# V2.net
KiCad netlist of a schematic drawn in EAGLE
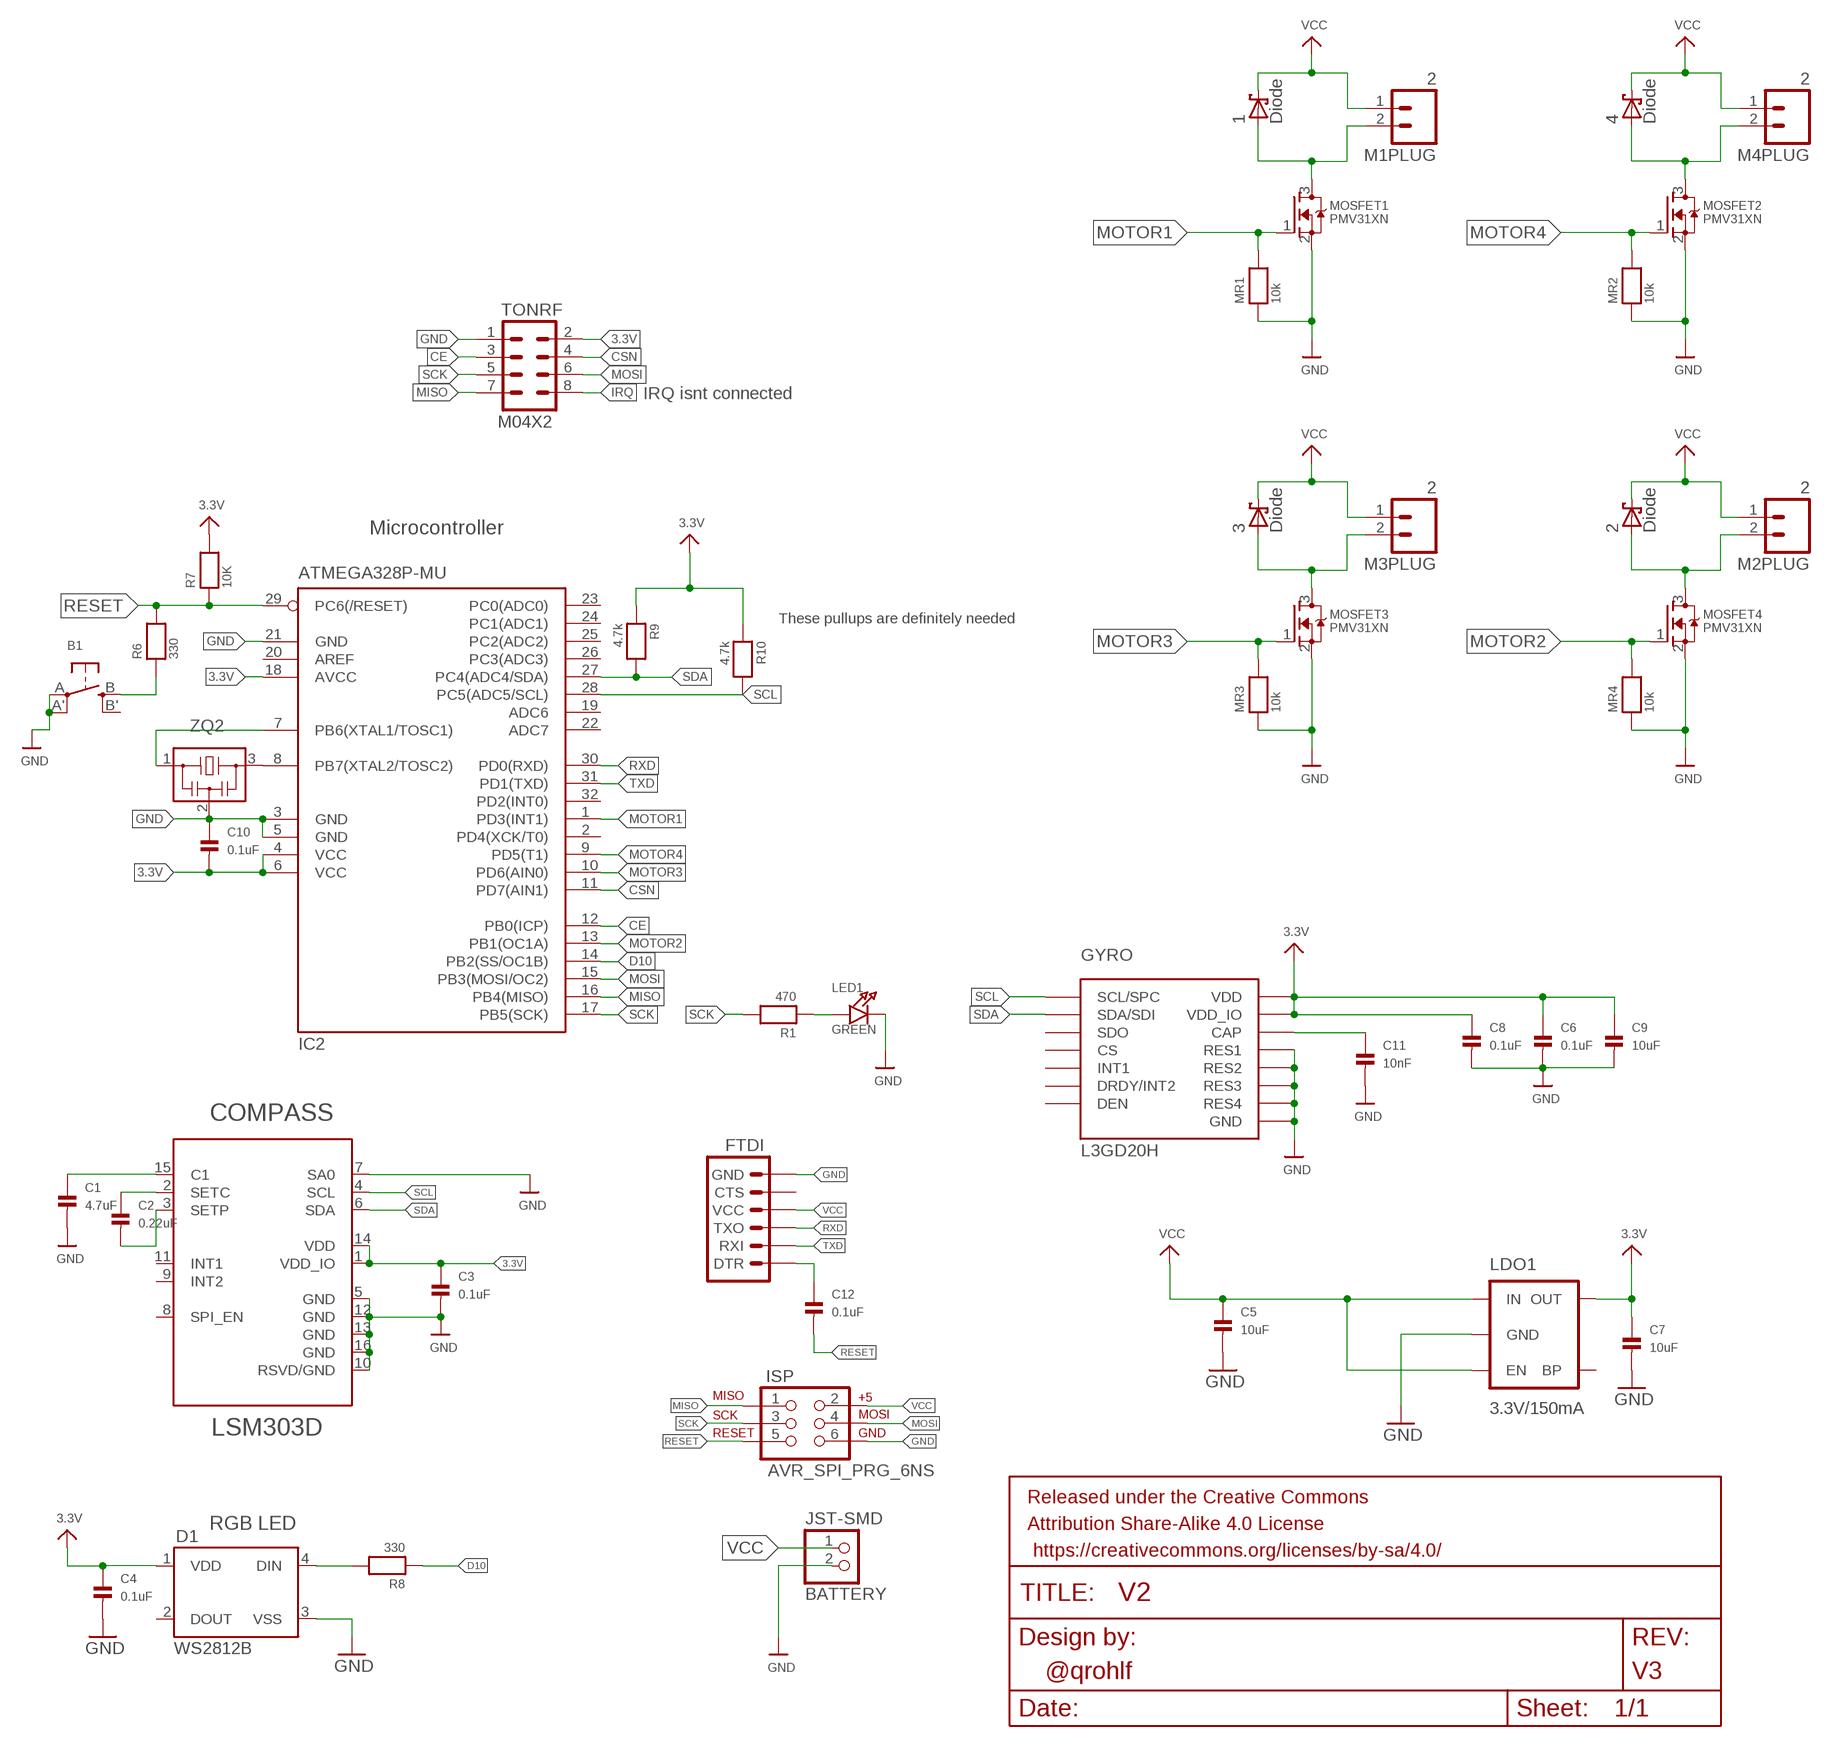
[diagram p0: schematic, sheet 1]

(export (version "E")
  (design (tool "Eeschema 10.0.6"))
  (components
    (comp (ref "1")
      (value "Diode")
      (footprint "eagle-import:SOT23")
      (libsource (lib "eagle-import") (part "BAS40"))
    )
    (comp (ref "2")
      (value "Diode")
      (footprint "eagle-import:SOT23")
      (libsource (lib "eagle-import") (part "BAS40"))
    )
    (comp (ref "3")
      (value "Diode")
      (footprint "eagle-import:SOT23")
      (libsource (lib "eagle-import") (part "BAS40"))
    )
    (comp (ref "4")
      (value "Diode")
      (footprint "eagle-import:SOT23")
      (libsource (lib "eagle-import") (part "BAS40"))
    )
    (comp (ref "B1")
      (value "SWITCH_TACT_SMT4.6X2.8")
      (footprint "eagle-import:BTN_KMR2_4.6X2.8")
      (libsource (lib "eagle-import") (part "SWITCH_TACT_SMT4.6X2.8"))
    )
    (comp (ref "BATTERY")
      (value "JST-SMD")
      (footprint "eagle-import:JST-PH-2-SMT-RA")
      (libsource (lib "eagle-import") (part "JST_2PIN-SMT-RA"))
    )
    (comp (ref "C1")
      (value "4.7uF")
      (footprint "eagle-import:0603-MINI")
      (libsource (lib "eagle-import") (part "CAP_CERAMIC0603MINI"))
    )
    (comp (ref "C2")
      (value "0.22uF")
      (footprint "eagle-import:0603-MINI")
      (libsource (lib "eagle-import") (part "CAP_CERAMIC0603MINI"))
    )
    (comp (ref "C3")
      (value "0.1uF")
      (footprint "eagle-import:0603-MINI")
      (libsource (lib "eagle-import") (part "CAP_CERAMIC0603MINI"))
    )
    (comp (ref "C4")
      (value "0.1uF")
      (footprint "eagle-import:0603-MINI")
      (libsource (lib "eagle-import") (part "CAP_CERAMIC0603MINI"))
    )
    (comp (ref "C5")
      (value "10uF")
      (footprint "eagle-import:0603-MINI")
      (libsource (lib "eagle-import") (part "CAP_CERAMIC0603MINI"))
    )
    (comp (ref "C6")
      (value "0.1uF")
      (footprint "eagle-import:0603-MINI")
      (libsource (lib "eagle-import") (part "CAP_CERAMIC0603MINI"))
    )
    (comp (ref "C7")
      (value "10uF")
      (footprint "eagle-import:0603-MINI")
      (libsource (lib "eagle-import") (part "CAP_CERAMIC0603MINI"))
    )
    (comp (ref "C8")
      (value "0.1uF")
      (footprint "eagle-import:0603-MINI")
      (libsource (lib "eagle-import") (part "CAP_CERAMIC0603MINI"))
    )
    (comp (ref "C9")
      (value "10uF")
      (footprint "eagle-import:0603-MINI")
      (libsource (lib "eagle-import") (part "CAP_CERAMIC0603MINI"))
    )
    (comp (ref "C10")
      (value "0.1uF")
      (footprint "eagle-import:0603-MINI")
      (libsource (lib "eagle-import") (part "CAP_CERAMIC0603MINI"))
    )
    (comp (ref "C11")
      (value "10nF")
      (footprint "eagle-import:0603-MINI")
      (libsource (lib "eagle-import") (part "CAP_CERAMIC0603MINI"))
    )
    (comp (ref "C12")
      (value "0.1uF")
      (footprint "eagle-import:0603-MINI")
      (libsource (lib "eagle-import") (part "CAP_CERAMIC0603MINI"))
    )
    (comp (ref "COMPASS")
      (value "LSM303D")
      (footprint "eagle-import:LGA16_3X5")
      (libsource (lib "eagle-import") (part "LSM303D"))
    )
    (comp (ref "D1")
      (value "WS2812B")
      (footprint "eagle-import:WS2812B")
      (libsource (lib "eagle-import") (part "WS2812B"))
    )
    (comp (ref "FRAME1")
      (value ">VERSION")
      (footprint "eagle-import:DUMMY")
      (fields (field (name "DESIGNER") "@qrohlf") (field (name "VERSION") "V3"))
      (libsource (lib "eagle-import") (part "FRAME-LETTERNO_PACKAGE"))
    )
    (comp (ref "FTDI")
      (value "ARDUINO_SERIAL_PROGRAMLOCK")
      (footprint "eagle-import:1X06_LOCK")
      (libsource (lib "eagle-import") (part "ARDUINO_SERIAL_PROGRAMLOCK"))
    )
    (comp (ref "IC2")
      (value "ATMEGA328P-MU")
      (footprint "eagle-import:TQFP32-08")
      (fields (field (name "MPN") "ATMEGA8-16AU"))
      (libsource (lib "eagle-import") (part "MEGA8-AI"))
    )
    (comp (ref "ISP")
      (value "AVR_SPI_PRG_6NS")
      (footprint "eagle-import:2X3-NS")
      (libsource (lib "eagle-import") (part "AVR_SPI_PRG_6NS"))
    )
    (comp (ref "L3GD20H")
      (value "L3GD20H")
      (footprint "eagle-import:LGA16L")
      (libsource (lib "eagle-import") (part "L3GD20H"))
    )
    (comp (ref "LDO1")
      (value "3.3V/150mA")
      (footprint "eagle-import:SOT23-5")
      (libsource (lib "eagle-import") (part "V_REG_MIC52053.3V"))
    )
    (comp (ref "LED1")
      (value "GREEN")
      (footprint "eagle-import:CHIPLED_0603")
      (libsource (lib "eagle-import") (part "LED0603"))
    )
    (comp (ref "M1PLUG")
      (value "2")
      (footprint "eagle-import:MOLEX-1X2_LOCK")
      (libsource (lib "eagle-import") (part "M02POLAR_LOCK"))
    )
    (comp (ref "M2PLUG")
      (value "2")
      (footprint "eagle-import:MOLEX-1X2_LOCK")
      (libsource (lib "eagle-import") (part "M02POLAR_LOCK"))
    )
    (comp (ref "M3PLUG")
      (value "2")
      (footprint "eagle-import:MOLEX-1X2_LOCK")
      (libsource (lib "eagle-import") (part "M02POLAR_LOCK"))
    )
    (comp (ref "M4PLUG")
      (value "2")
      (footprint "eagle-import:MOLEX-1X2_LOCK")
      (libsource (lib "eagle-import") (part "M02POLAR_LOCK"))
    )
    (comp (ref "MOSFET1")
      (value "PMV31XN")
      (footprint "eagle-import:SOT23-R")
      (libsource (lib "eagle-import") (part "MOSFET-NREFLOW"))
    )
    (comp (ref "MOSFET2")
      (value "PMV31XN")
      (footprint "eagle-import:SOT23-R")
      (libsource (lib "eagle-import") (part "MOSFET-NREFLOW"))
    )
    (comp (ref "MOSFET3")
      (value "PMV31XN")
      (footprint "eagle-import:SOT23-R")
      (libsource (lib "eagle-import") (part "MOSFET-NREFLOW"))
    )
    (comp (ref "MOSFET4")
      (value "PMV31XN")
      (footprint "eagle-import:SOT23-R")
      (libsource (lib "eagle-import") (part "MOSFET-NREFLOW"))
    )
    (comp (ref "MR1")
      (value "10k")
      (footprint "eagle-import:0603-MINI")
      (libsource (lib "eagle-import") (part "RESISTOR0603MINI"))
    )
    (comp (ref "MR2")
      (value "10k")
      (footprint "eagle-import:0603-MINI")
      (libsource (lib "eagle-import") (part "RESISTOR0603MINI"))
    )
    (comp (ref "MR3")
      (value "10k")
      (footprint "eagle-import:0603-MINI")
      (libsource (lib "eagle-import") (part "RESISTOR0603MINI"))
    )
    (comp (ref "MR4")
      (value "10k")
      (footprint "eagle-import:0603-MINI")
      (libsource (lib "eagle-import") (part "RESISTOR0603MINI"))
    )
    (comp (ref "R1")
      (value "470")
      (footprint "eagle-import:0603-MINI")
      (libsource (lib "eagle-import") (part "RESISTOR0603MINI"))
    )
    (comp (ref "R6")
      (value "330")
      (footprint "eagle-import:0603-MINI")
      (libsource (lib "eagle-import") (part "RESISTOR0603MINI"))
    )
    (comp (ref "R7")
      (value "10K")
      (footprint "eagle-import:0603-MINI")
      (libsource (lib "eagle-import") (part "RESISTOR0603MINI"))
    )
    (comp (ref "R8")
      (value "330")
      (footprint "eagle-import:0603-MINI")
      (libsource (lib "eagle-import") (part "RESISTOR0603MINI"))
    )
    (comp (ref "R9")
      (value "4.7k")
      (footprint "eagle-import:0603-MINI")
      (libsource (lib "eagle-import") (part "RESISTOR0603MINI"))
    )
    (comp (ref "R10")
      (value "4.7k")
      (footprint "eagle-import:0603-MINI")
      (libsource (lib "eagle-import") (part "RESISTOR0603MINI"))
    )
    (comp (ref "TONRF")
      (value "M04X2")
      (footprint "eagle-import:2X4")
      (libsource (lib "eagle-import") (part "M04X2"))
    )
    (comp (ref "ZQ2")
      (value "CSTCE8M00G52-R0")
      (footprint "eagle-import:CSTCE")
      (libsource (lib "eagle-import") (part "CSTC?E8M00G52-R0"))
    )
  )
  (nets
    (net (code "1") (name "3.3V") (class "Default")
      (node (ref "C10") (pin "2") (pinfunction "P$2_2") (pintype "passive"))
      (node (ref "C3") (pin "1") (pinfunction "P$1_1") (pintype "passive"))
      (node (ref "C4") (pin "1") (pinfunction "P$1_1") (pintype "passive"))
      (node (ref "C6") (pin "1") (pinfunction "P$1_1") (pintype "passive"))
      (node (ref "C7") (pin "1") (pinfunction "P$1_1") (pintype "passive"))
      (node (ref "C8") (pin "1") (pinfunction "P$1_1") (pintype "passive"))
      (node (ref "C9") (pin "1") (pinfunction "P$1_1") (pintype "passive"))
      (node (ref "COMPASS") (pin "1") (pinfunction "VDD_IO_1") (pintype "power_in"))
      (node (ref "COMPASS") (pin "14") (pinfunction "VDD_14") (pintype "power_in"))
      (node (ref "D1") (pin "1") (pinfunction "VDD_1") (pintype "power_in"))
      (node (ref "IC2") (pin "18") (pinfunction "AVCC_18") (pintype "power_in"))
      (node (ref "IC2") (pin "4") (pinfunction "VCC_4") (pintype "power_in"))
      (node (ref "IC2") (pin "6") (pinfunction "VCC_6") (pintype "power_in"))
      (node (ref "L3GD20H") (pin "P$1") (pinfunction "VDD_IO_P$1") (pintype "power_in"))
      (node (ref "L3GD20H") (pin "P$16") (pinfunction "VDD_P$16") (pintype "power_in"))
      (node (ref "LDO1") (pin "5") (pinfunction "OUT_5") (pintype "passive"))
      (node (ref "R10") (pin "1") (pinfunction "1_1") (pintype "passive"))
      (node (ref "R7") (pin "2") (pinfunction "2_2") (pintype "passive"))
      (node (ref "R9") (pin "1") (pinfunction "1_1") (pintype "passive"))
      (node (ref "TONRF") (pin "2") (pinfunction "2_2") (pintype "passive"))
    )
    (net (code "2") (name "CE") (class "Default")
      (node (ref "IC2") (pin "12") (pinfunction "PB0(ICP)_12") (pintype "bidirectional"))
      (node (ref "TONRF") (pin "3") (pinfunction "3_3") (pintype "passive"))
    )
    (net (code "3") (name "CSN") (class "Default")
      (node (ref "IC2") (pin "11") (pinfunction "PD7(AIN1)_11") (pintype "bidirectional"))
      (node (ref "TONRF") (pin "4") (pinfunction "4_4") (pintype "passive"))
    )
    (net (code "4") (name "D10") (class "Default")
      (node (ref "IC2") (pin "14") (pinfunction "PB2(SS/OC1B)_14") (pintype "bidirectional"))
      (node (ref "R8") (pin "1") (pinfunction "1_1") (pintype "passive"))
    )
    (net (code "5") (name "GND") (class "Default")
      (node (ref "B1") (pin "A") (pinfunction "P_A") (pintype "passive"))
      (node (ref "B1") (pin "A'") (pinfunction "P1_A'") (pintype "passive"))
      (node (ref "BATTERY") (pin "2") (pinfunction "1_2") (pintype "passive"))
      (node (ref "C1") (pin "2") (pinfunction "P$2_2") (pintype "passive"))
      (node (ref "C10") (pin "1") (pinfunction "P$1_1") (pintype "passive"))
      (node (ref "C11") (pin "2") (pinfunction "P$2_2") (pintype "passive"))
      (node (ref "C3") (pin "2") (pinfunction "P$2_2") (pintype "passive"))
      (node (ref "C4") (pin "2") (pinfunction "P$2_2") (pintype "passive"))
      (node (ref "C5") (pin "2") (pinfunction "P$2_2") (pintype "passive"))
      (node (ref "C6") (pin "2") (pinfunction "P$2_2") (pintype "passive"))
      (node (ref "C7") (pin "2") (pinfunction "P$2_2") (pintype "passive"))
      (node (ref "C8") (pin "2") (pinfunction "P$2_2") (pintype "passive"))
      (node (ref "C9") (pin "2") (pinfunction "P$2_2") (pintype "passive"))
      (node (ref "COMPASS") (pin "10") (pinfunction "RSVD/GND_10") (pintype "bidirectional"))
      (node (ref "COMPASS") (pin "12") (pinfunction "GND_12") (pintype "power_in"))
      (node (ref "COMPASS") (pin "13") (pinfunction "GND_13") (pintype "power_in"))
      (node (ref "COMPASS") (pin "16") (pinfunction "GND_16") (pintype "power_in"))
      (node (ref "COMPASS") (pin "5") (pinfunction "GND_5") (pintype "power_in"))
      (node (ref "COMPASS") (pin "7") (pinfunction "SA0_7") (pintype "bidirectional"))
      (node (ref "D1") (pin "3") (pinfunction "VSS_3") (pintype "power_in"))
      (node (ref "FTDI") (pin "6") (pinfunction "GND_6") (pintype "passive"))
      (node (ref "IC2") (pin "21") (pinfunction "GND_21") (pintype "power_in"))
      (node (ref "IC2") (pin "3") (pinfunction "GND_3") (pintype "power_in"))
      (node (ref "IC2") (pin "5") (pinfunction "GND_5") (pintype "power_in"))
      (node (ref "ISP") (pin "6") (pinfunction "6_6") (pintype "passive"))
      (node (ref "L3GD20H") (pin "P$10") (pinfunction "RES2_P$10") (pintype "bidirectional"))
      (node (ref "L3GD20H") (pin "P$11") (pinfunction "RES3_P$11") (pintype "bidirectional"))
      (node (ref "L3GD20H") (pin "P$12") (pinfunction "GND_P$12") (pintype "power_in"))
      (node (ref "L3GD20H") (pin "P$13") (pinfunction "GND_P$13") (pintype "power_in"))
      (node (ref "L3GD20H") (pin "P$15") (pinfunction "RES4_P$15") (pintype "bidirectional"))
      (node (ref "L3GD20H") (pin "P$9") (pinfunction "RES1_P$9") (pintype "bidirectional"))
      (node (ref "LDO1") (pin "2") (pinfunction "GND_2") (pintype "input"))
      (node (ref "LED1") (pin "C") (pinfunction "C_C") (pintype "passive"))
      (node (ref "MOSFET1") (pin "2") (pinfunction "S_2") (pintype "bidirectional"))
      (node (ref "MOSFET2") (pin "2") (pinfunction "S_2") (pintype "bidirectional"))
      (node (ref "MOSFET3") (pin "2") (pinfunction "S_2") (pintype "bidirectional"))
      (node (ref "MOSFET4") (pin "2") (pinfunction "S_2") (pintype "bidirectional"))
      (node (ref "MR1") (pin "1") (pinfunction "1_1") (pintype "passive"))
      (node (ref "MR2") (pin "1") (pinfunction "1_1") (pintype "passive"))
      (node (ref "MR3") (pin "1") (pinfunction "1_1") (pintype "passive"))
      (node (ref "MR4") (pin "1") (pinfunction "1_1") (pintype "passive"))
      (node (ref "TONRF") (pin "1") (pinfunction "1_1") (pintype "passive"))
      (node (ref "ZQ2") (pin "2") (pinfunction "2_2") (pintype "passive"))
    )
    (net (code "6") (name "IRQ") (class "Default")
      (node (ref "TONRF") (pin "8") (pinfunction "8_8") (pintype "passive"))
    )
    (net (code "7") (name "MISO") (class "Default")
      (node (ref "IC2") (pin "16") (pinfunction "PB4(MISO)_16") (pintype "bidirectional"))
      (node (ref "ISP") (pin "1") (pinfunction "1_1") (pintype "passive"))
      (node (ref "TONRF") (pin "7") (pinfunction "7_7") (pintype "passive"))
    )
    (net (code "8") (name "MOSI") (class "Default")
      (node (ref "IC2") (pin "15") (pinfunction "PB3(MOSI/OC2)_15") (pintype "bidirectional"))
      (node (ref "ISP") (pin "4") (pinfunction "4_4") (pintype "passive"))
      (node (ref "TONRF") (pin "6") (pinfunction "6_6") (pintype "passive"))
    )
    (net (code "9") (name "MOTOR1") (class "Default")
      (node (ref "IC2") (pin "1") (pinfunction "PD3(INT1)_1") (pintype "bidirectional"))
      (node (ref "MOSFET1") (pin "1") (pinfunction "G_1") (pintype "bidirectional"))
      (node (ref "MR1") (pin "2") (pinfunction "2_2") (pintype "passive"))
    )
    (net (code "10") (name "MOTOR2") (class "Default")
      (node (ref "IC2") (pin "13") (pinfunction "PB1(OC1A)_13") (pintype "bidirectional"))
      (node (ref "MOSFET4") (pin "1") (pinfunction "G_1") (pintype "bidirectional"))
      (node (ref "MR4") (pin "2") (pinfunction "2_2") (pintype "passive"))
    )
    (net (code "11") (name "MOTOR3") (class "Default")
      (node (ref "IC2") (pin "10") (pinfunction "PD6(AIN0)_10") (pintype "bidirectional"))
      (node (ref "MOSFET3") (pin "1") (pinfunction "G_1") (pintype "bidirectional"))
      (node (ref "MR3") (pin "2") (pinfunction "2_2") (pintype "passive"))
    )
    (net (code "12") (name "MOTOR4") (class "Default")
      (node (ref "IC2") (pin "9") (pinfunction "PD5(T1)_9") (pintype "bidirectional"))
      (node (ref "MOSFET2") (pin "1") (pinfunction "G_1") (pintype "bidirectional"))
      (node (ref "MR2") (pin "2") (pinfunction "2_2") (pintype "passive"))
    )
    (net (code "13") (name "Net-(1-A)") (class "Default")
      (node (ref "1") (pin "1") (pinfunction "A_1") (pintype "passive"))
      (node (ref "M1PLUG") (pin "2") (pinfunction "2_2") (pintype "passive"))
      (node (ref "MOSFET1") (pin "3") (pinfunction "D_3") (pintype "bidirectional"))
    )
    (net (code "14") (name "Net-(2-A)") (class "Default")
      (node (ref "2") (pin "1") (pinfunction "A_1") (pintype "passive"))
      (node (ref "M2PLUG") (pin "2") (pinfunction "2_2") (pintype "passive"))
      (node (ref "MOSFET4") (pin "3") (pinfunction "D_3") (pintype "bidirectional"))
    )
    (net (code "15") (name "Net-(3-A)") (class "Default")
      (node (ref "3") (pin "1") (pinfunction "A_1") (pintype "passive"))
      (node (ref "M3PLUG") (pin "2") (pinfunction "2_2") (pintype "passive"))
      (node (ref "MOSFET3") (pin "3") (pinfunction "D_3") (pintype "bidirectional"))
    )
    (net (code "16") (name "Net-(4-A)") (class "Default")
      (node (ref "4") (pin "1") (pinfunction "A_1") (pintype "passive"))
      (node (ref "M4PLUG") (pin "2") (pinfunction "2_2") (pintype "passive"))
      (node (ref "MOSFET2") (pin "3") (pinfunction "D_3") (pintype "bidirectional"))
    )
    (net (code "17") (name "Net-(B1-S)") (class "Default")
      (node (ref "B1") (pin "B") (pinfunction "S_B") (pintype "passive"))
      (node (ref "R6") (pin "1") (pinfunction "1_1") (pintype "passive"))
    )
    (net (code "18") (name "Net-(C1-P$1)") (class "Default")
      (node (ref "C1") (pin "1") (pinfunction "P$1_1") (pintype "passive"))
      (node (ref "COMPASS") (pin "15") (pinfunction "C1_15") (pintype "bidirectional"))
    )
    (net (code "19") (name "Net-(C2-P$1)") (class "Default")
      (node (ref "C2") (pin "1") (pinfunction "P$1_1") (pintype "passive"))
      (node (ref "COMPASS") (pin "2") (pinfunction "SETC_2") (pintype "bidirectional"))
    )
    (net (code "20") (name "Net-(C2-P$2)") (class "Default")
      (node (ref "C2") (pin "2") (pinfunction "P$2_2") (pintype "passive"))
      (node (ref "COMPASS") (pin "3") (pinfunction "SETP_3") (pintype "bidirectional"))
    )
    (net (code "21") (name "Net-(C11-P$1)") (class "Default")
      (node (ref "C11") (pin "1") (pinfunction "P$1_1") (pintype "passive"))
      (node (ref "L3GD20H") (pin "P$14") (pinfunction "CAP_P$14") (pintype "bidirectional"))
    )
    (net (code "22") (name "Net-(C12-P$1)") (class "Default")
      (node (ref "C12") (pin "1") (pinfunction "P$1_1") (pintype "passive"))
      (node (ref "FTDI") (pin "1") (pinfunction "DTR_1") (pintype "passive"))
    )
    (net (code "23") (name "Net-(D1-DIN)") (class "Default")
      (node (ref "D1") (pin "4") (pinfunction "DIN_4") (pintype "input"))
      (node (ref "R8") (pin "2") (pinfunction "2_2") (pintype "passive"))
    )
    (net (code "24") (name "Net-(IC2-PB6(XTAL1{slash}TOSC1))") (class "Default")
      (node (ref "IC2") (pin "7") (pinfunction "PB6(XTAL1/TOSC1)_7") (pintype "bidirectional"))
      (node (ref "ZQ2") (pin "1") (pinfunction "1_1") (pintype "passive"))
    )
    (net (code "25") (name "Net-(IC2-PB7(XTAL2{slash}TOSC2))") (class "Default")
      (node (ref "IC2") (pin "8") (pinfunction "PB7(XTAL2/TOSC2)_8") (pintype "bidirectional"))
      (node (ref "ZQ2") (pin "3") (pinfunction "3_3") (pintype "passive"))
    )
    (net (code "26") (name "Net-(LED1-PadA)") (class "Default")
      (node (ref "LED1") (pin "A") (pinfunction "A_A") (pintype "passive"))
      (node (ref "R1") (pin "1") (pinfunction "1_1") (pintype "passive"))
    )
    (net (code "27") (name "RESET") (class "Default")
      (node (ref "C12") (pin "2") (pinfunction "P$2_2") (pintype "passive"))
      (node (ref "IC2") (pin "29") (pinfunction "PC6(/RESET)_29") (pintype "bidirectional"))
      (node (ref "ISP") (pin "5") (pinfunction "5_5") (pintype "passive"))
      (node (ref "R6") (pin "2") (pinfunction "2_2") (pintype "passive"))
      (node (ref "R7") (pin "1") (pinfunction "1_1") (pintype "passive"))
    )
    (net (code "28") (name "RXD") (class "Default")
      (node (ref "FTDI") (pin "3") (pinfunction "TXO_3") (pintype "passive"))
      (node (ref "IC2") (pin "30") (pinfunction "PD0(RXD)_30") (pintype "bidirectional"))
    )
    (net (code "29") (name "SCK") (class "Default")
      (node (ref "IC2") (pin "17") (pinfunction "PB5(SCK)_17") (pintype "bidirectional"))
      (node (ref "ISP") (pin "3") (pinfunction "3_3") (pintype "passive"))
      (node (ref "R1") (pin "2") (pinfunction "2_2") (pintype "passive"))
      (node (ref "TONRF") (pin "5") (pinfunction "5_5") (pintype "passive"))
    )
    (net (code "30") (name "SCL") (class "Default")
      (node (ref "COMPASS") (pin "4") (pinfunction "SCL_4") (pintype "bidirectional"))
      (node (ref "IC2") (pin "28") (pinfunction "PC5(ADC5/SCL)_28") (pintype "bidirectional"))
      (node (ref "L3GD20H") (pin "P$2") (pinfunction "SCL/SPC_P$2") (pintype "bidirectional"))
      (node (ref "R10") (pin "2") (pinfunction "2_2") (pintype "passive"))
    )
    (net (code "31") (name "SDA") (class "Default")
      (node (ref "COMPASS") (pin "6") (pinfunction "SDA_6") (pintype "bidirectional"))
      (node (ref "IC2") (pin "27") (pinfunction "PC4(ADC4/SDA)_27") (pintype "bidirectional"))
      (node (ref "L3GD20H") (pin "P$3") (pinfunction "SDA/SDI_P$3") (pintype "bidirectional"))
      (node (ref "R9") (pin "2") (pinfunction "2_2") (pintype "passive"))
    )
    (net (code "32") (name "TXD") (class "Default")
      (node (ref "FTDI") (pin "2") (pinfunction "RXI_2") (pintype "passive"))
      (node (ref "IC2") (pin "31") (pinfunction "PD1(TXD)_31") (pintype "bidirectional"))
    )
    (net (code "33") (name "VCC") (class "Default")
      (node (ref "1") (pin "3") (pinfunction "C_3") (pintype "passive"))
      (node (ref "2") (pin "3") (pinfunction "C_3") (pintype "passive"))
      (node (ref "3") (pin "3") (pinfunction "C_3") (pintype "passive"))
      (node (ref "4") (pin "3") (pinfunction "C_3") (pintype "passive"))
      (node (ref "BATTERY") (pin "1") (pinfunction "2_1") (pintype "passive"))
      (node (ref "C5") (pin "1") (pinfunction "P$1_1") (pintype "passive"))
      (node (ref "FTDI") (pin "4") (pinfunction "VCC_4") (pintype "passive"))
      (node (ref "ISP") (pin "2") (pinfunction "2_2") (pintype "passive"))
      (node (ref "LDO1") (pin "1") (pinfunction "IN_1") (pintype "input"))
      (node (ref "LDO1") (pin "3") (pinfunction "EN_3") (pintype "input"))
      (node (ref "M1PLUG") (pin "1") (pinfunction "1_1") (pintype "passive"))
      (node (ref "M2PLUG") (pin "1") (pinfunction "1_1") (pintype "passive"))
      (node (ref "M3PLUG") (pin "1") (pinfunction "1_1") (pintype "passive"))
      (node (ref "M4PLUG") (pin "1") (pinfunction "1_1") (pintype "passive"))
    )
    (net (code "34") (name "unconnected-(B1-S1-PadB')") (class "Default")
      (node (ref "B1") (pin "B'") (pinfunction "S1_B'") (pintype "passive"))
    )
    (net (code "35") (name "unconnected-(COMPASS-INT1-Pad11)") (class "Default")
      (node (ref "COMPASS") (pin "11") (pinfunction "INT1_11") (pintype "bidirectional"))
    )
    (net (code "36") (name "unconnected-(COMPASS-INT2-Pad9)") (class "Default")
      (node (ref "COMPASS") (pin "9") (pinfunction "INT2_9") (pintype "bidirectional"))
    )
    (net (code "37") (name "unconnected-(COMPASS-SPI_EN-Pad8)") (class "Default")
      (node (ref "COMPASS") (pin "8") (pinfunction "SPI_EN_8") (pintype "bidirectional"))
    )
    (net (code "38") (name "unconnected-(D1-DOUT-Pad2)") (class "Default")
      (node (ref "D1") (pin "2") (pinfunction "DOUT_2") (pintype "output"))
    )
    (net (code "39") (name "unconnected-(FTDI-CTS-Pad5)") (class "Default")
      (node (ref "FTDI") (pin "5") (pinfunction "CTS_5") (pintype "passive"))
    )
    (net (code "40") (name "unconnected-(IC2-ADC6-Pad19)") (class "Default")
      (node (ref "IC2") (pin "19") (pinfunction "ADC6_19") (pintype "bidirectional"))
    )
    (net (code "41") (name "unconnected-(IC2-ADC7-Pad22)") (class "Default")
      (node (ref "IC2") (pin "22") (pinfunction "ADC7_22") (pintype "bidirectional"))
    )
    (net (code "42") (name "unconnected-(IC2-AREF-Pad20)") (class "Default")
      (node (ref "IC2") (pin "20") (pinfunction "AREF_20") (pintype "passive"))
    )
    (net (code "43") (name "unconnected-(IC2-PC0(ADC0)-Pad23)") (class "Default")
      (node (ref "IC2") (pin "23") (pinfunction "PC0(ADC0)_23") (pintype "bidirectional"))
    )
    (net (code "44") (name "unconnected-(IC2-PC1(ADC1)-Pad24)") (class "Default")
      (node (ref "IC2") (pin "24") (pinfunction "PC1(ADC1)_24") (pintype "bidirectional"))
    )
    (net (code "45") (name "unconnected-(IC2-PC2(ADC2)-Pad25)") (class "Default")
      (node (ref "IC2") (pin "25") (pinfunction "PC2(ADC2)_25") (pintype "bidirectional"))
    )
    (net (code "46") (name "unconnected-(IC2-PC3(ADC3)-Pad26)") (class "Default")
      (node (ref "IC2") (pin "26") (pinfunction "PC3(ADC3)_26") (pintype "bidirectional"))
    )
    (net (code "47") (name "unconnected-(IC2-PD2(INT0)-Pad32)") (class "Default")
      (node (ref "IC2") (pin "32") (pinfunction "PD2(INT0)_32") (pintype "bidirectional"))
    )
    (net (code "48") (name "unconnected-(IC2-PD4(XCK{slash}T0)-Pad2)") (class "Default")
      (node (ref "IC2") (pin "2") (pinfunction "PD4(XCK/T0)_2") (pintype "bidirectional"))
    )
    (net (code "49") (name "unconnected-(L3GD20H-CS-PadP$5)") (class "Default")
      (node (ref "L3GD20H") (pin "P$5") (pinfunction "CS_P$5") (pintype "bidirectional"))
    )
    (net (code "50") (name "unconnected-(L3GD20H-DEN-PadP$8)") (class "Default")
      (node (ref "L3GD20H") (pin "P$8") (pinfunction "DEN_P$8") (pintype "bidirectional"))
    )
    (net (code "51") (name "unconnected-(L3GD20H-DRDY{slash}INT2-PadP$6)") (class "Default")
      (node (ref "L3GD20H") (pin "P$6") (pinfunction "DRDY/INT2_P$6") (pintype "bidirectional"))
    )
    (net (code "52") (name "unconnected-(L3GD20H-INT1-PadP$7)") (class "Default")
      (node (ref "L3GD20H") (pin "P$7") (pinfunction "INT1_P$7") (pintype "bidirectional"))
    )
    (net (code "53") (name "unconnected-(L3GD20H-SDO-PadP$4)") (class "Default")
      (node (ref "L3GD20H") (pin "P$4") (pinfunction "SDO_P$4") (pintype "bidirectional"))
    )
    (net (code "54") (name "unconnected-(LDO1-BP-Pad4)") (class "Default")
      (node (ref "LDO1") (pin "4") (pinfunction "BP_4") (pintype "input"))
    )
  )
)
